# oscillator.net
KiCad netlist of a schematic drawn in Altium Designer
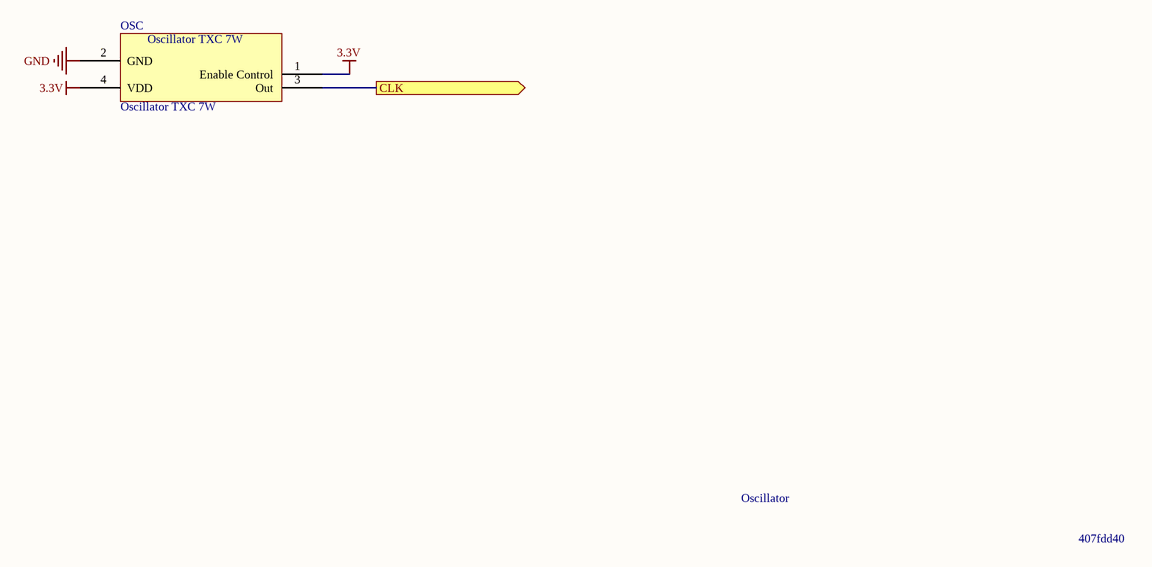
[diagram p0: oscillator.SchDoc]

(export (version "E")
  (design (tool "Eeschema 10.0.6"))
  (components
    (comp (ref "OSC")
      (value "Oscillator TXC 7W")
      (footprint "TXC - 7W-60.000MBB-T")
      (libsource (lib "oscillator") (part "Oscillator TXC 7W"))
    )
  )
  (nets
    (net (code "1") (name "/CLK") (class "Default")
      (node (ref "OSC") (pin "3") (pinfunction "Out_3") (pintype "passive"))
    )
    (net (code "2") (name "3.3V") (class "Default")
      (node (ref "OSC") (pin "1") (pinfunction "Enable_Control_1") (pintype "passive"))
      (node (ref "OSC") (pin "4") (pinfunction "VDD_4") (pintype "passive"))
    )
    (net (code "3") (name "GND") (class "Default")
      (node (ref "OSC") (pin "2") (pinfunction "GND_2") (pintype "passive"))
    )
  )
)
